# Unused_Modem_Pins.net
KiCad netlist of a schematic drawn in Altium Designer
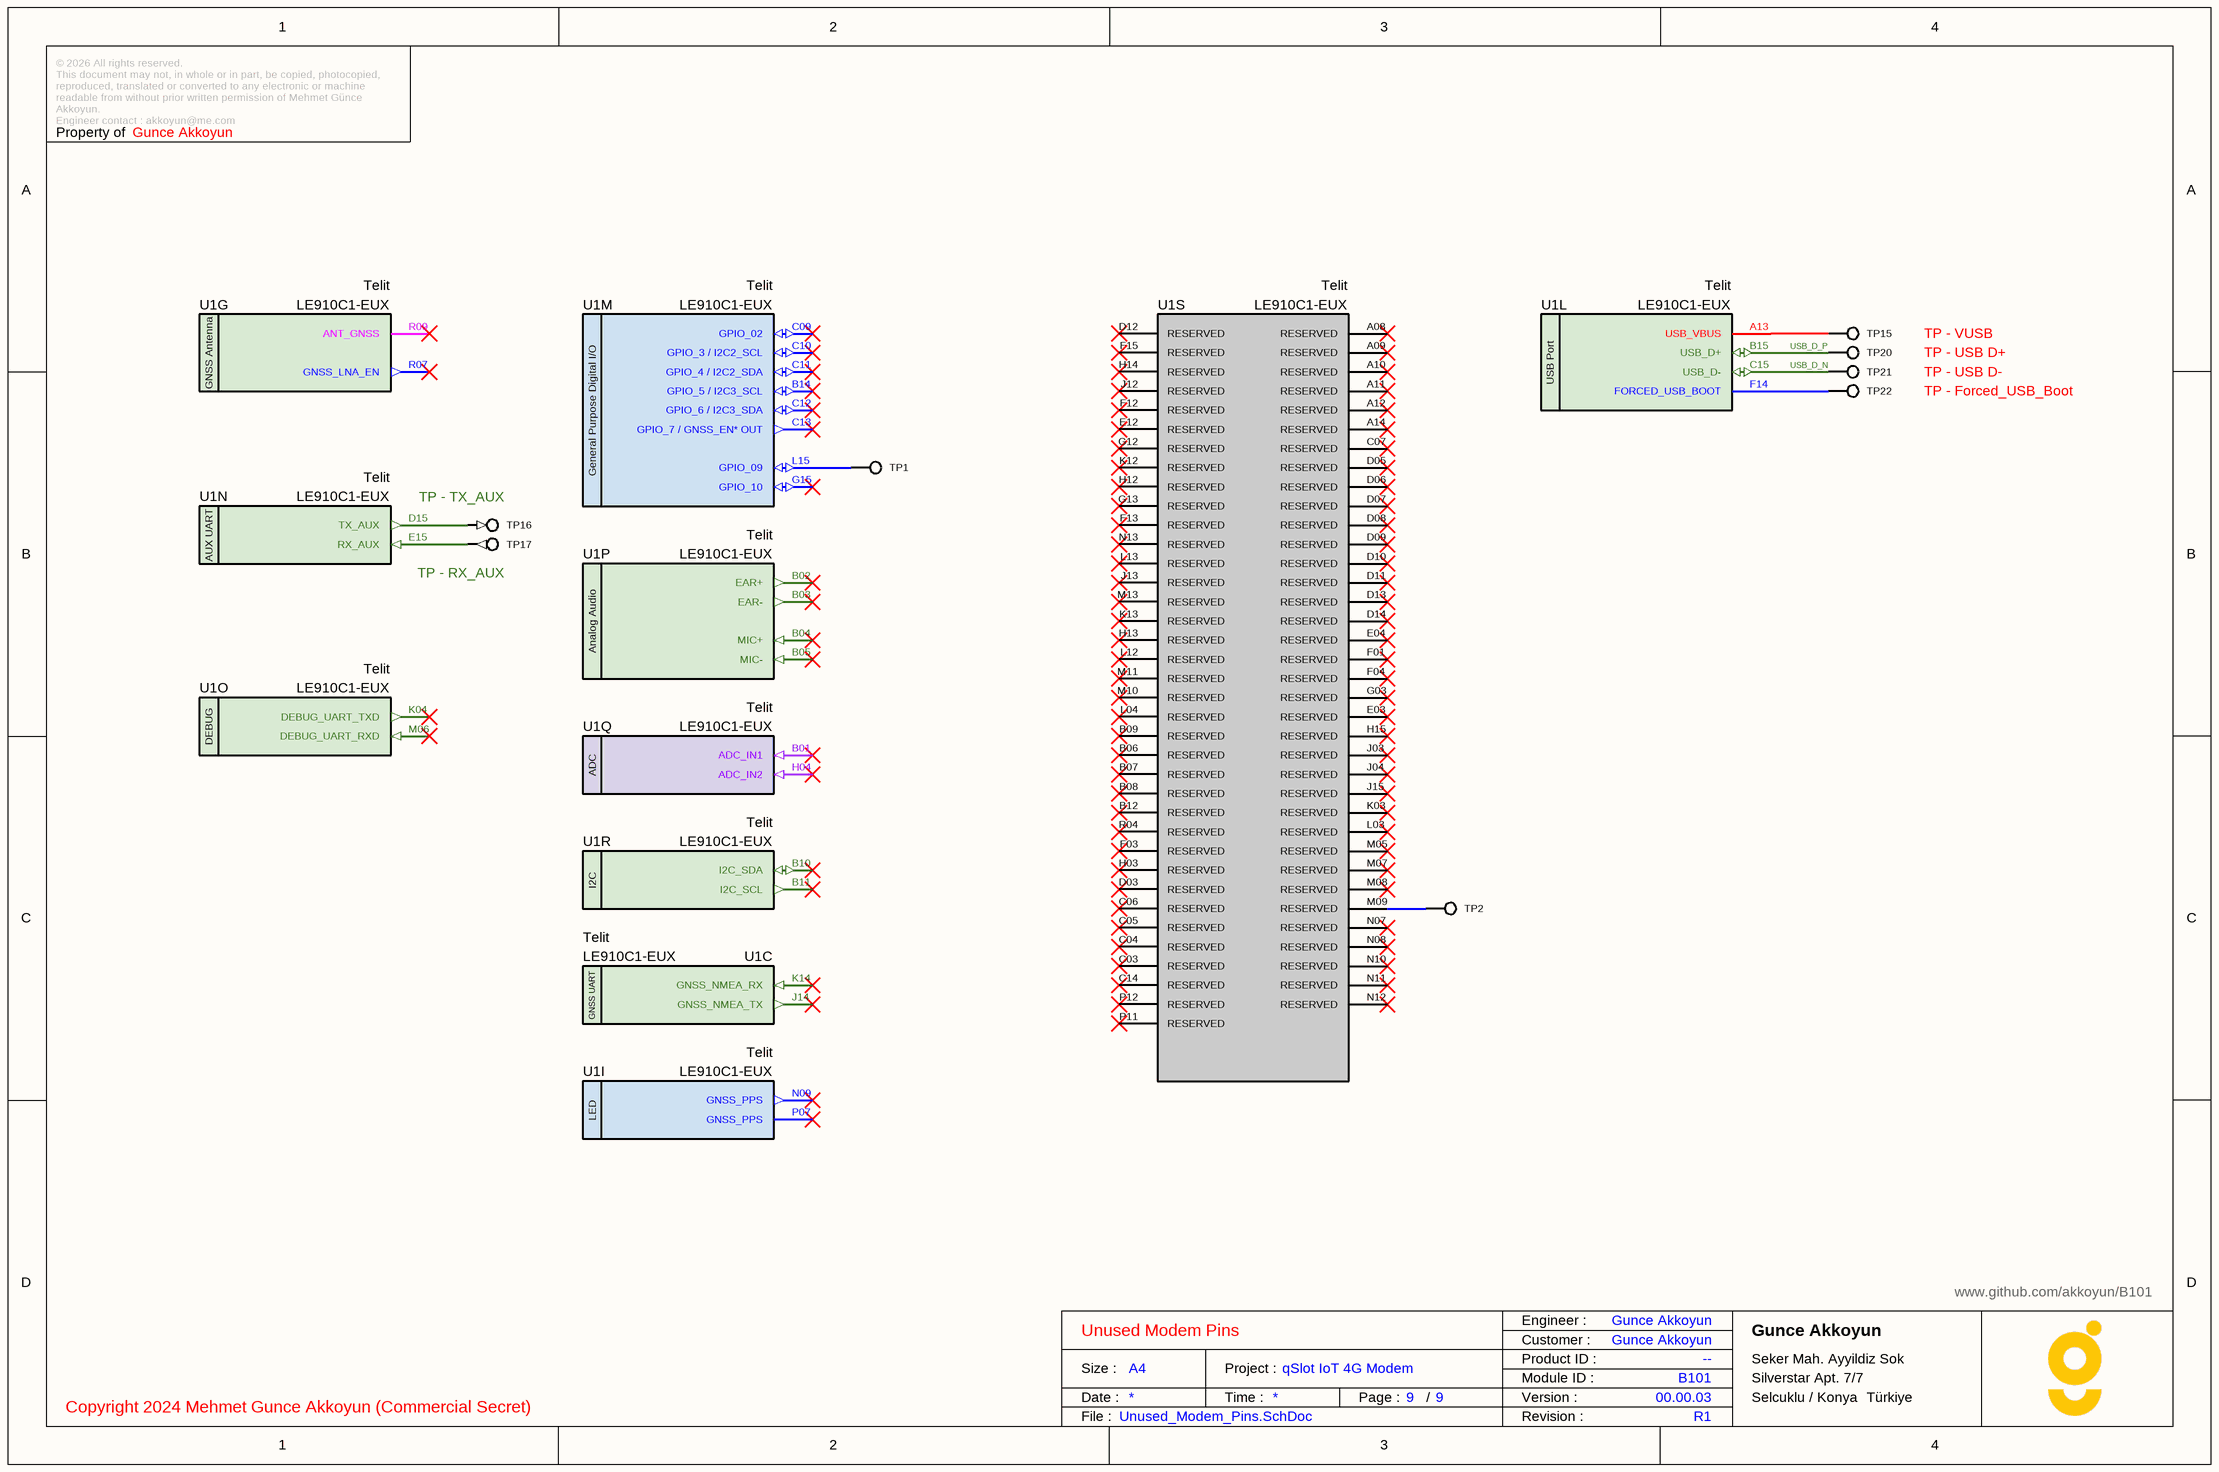
[diagram p0: Unused_Modem_Pins.SchDoc]

(export (version "E")
  (design (tool "Eeschema 10.0.6"))
  (components
    (comp (ref "TP1")
      (value "PCB - Test Point")
      (footprint "TP")
      (description "Test Point")
      (libsource (lib "Akkoyun") (part "PCB - Test Point"))
    )
    (comp (ref "TP2")
      (value "PCB - Test Point")
      (footprint "TP")
      (description "Test Point")
      (libsource (lib "Akkoyun") (part "PCB - Test Point"))
    )
    (comp (ref "TP15")
      (value "TP - VUSB")
      (footprint "TP")
      (description "Test Point")
      (libsource (lib "Akkoyun") (part "PCB - Test Point"))
    )
    (comp (ref "TP16")
      (value "TP - TX_AUX")
      (footprint "TP")
      (description "Test Point")
      (libsource (lib "Akkoyun") (part "PCB - Test Point"))
    )
    (comp (ref "TP17")
      (value "TP - RX_AUX")
      (footprint "TP")
      (description "Test Point")
      (libsource (lib "Akkoyun") (part "PCB - Test Point"))
    )
    (comp (ref "TP20")
      (value "TP - USB D+")
      (footprint "TP")
      (description "Test Point")
      (libsource (lib "Akkoyun") (part "PCB - Test Point"))
    )
    (comp (ref "TP21")
      (value "TP - USB D-")
      (footprint "TP")
      (description "Test Point")
      (libsource (lib "Akkoyun") (part "PCB - Test Point"))
    )
    (comp (ref "TP22")
      (value "TP - Forced_USB_Boot")
      (footprint "TP")
      (description "Test Point")
      (libsource (lib "Akkoyun") (part "PCB - Test Point"))
    )
    (comp (ref "U1")
      (value "LE910C1-EUX LTE GSM Module")
      (footprint "LE910 GSM Modem")
      (description "Telit LE910C1-EUX LTE/2G GSM Module")
      (fields
        (field (name "MANUFACTURER PART NUMBER") "LE910C1-EUX")
        (field (name "MANUFACTURER NAME") "Telit")
      )
      (libsource (lib "Akkoyun") (part "IC - LE910C1-EUX"))
    )
  )
  (nets
    (net (code "1") (name "/USB_D_N") (class "Default")
      (node (ref "TP21") (pin "1") (pinfunction "1_1") (pintype "output"))
      (node (ref "U1") (pin "C15") (pinfunction "USB_D-_C15") (pintype "bidirectional"))
    )
    (net (code "2") (name "/USB_D_P") (class "Default")
      (node (ref "TP20") (pin "1") (pinfunction "1_1") (pintype "output"))
      (node (ref "U1") (pin "B15") (pinfunction "USB_D+_B15") (pintype "bidirectional"))
    )
    (net (code "3") (name "Net-(TP2-Pad1)") (class "Default")
      (node (ref "TP2") (pin "1") (pinfunction "1_1") (pintype "output"))
      (node (ref "U1") (pin "M09") (pinfunction "RESERVED_M09") (pintype "passive"))
    )
    (net (code "4") (name "Net-(U1L-FORCED_USB_BOOT)") (class "Default")
      (node (ref "TP22") (pin "1") (pinfunction "1_1") (pintype "output"))
      (node (ref "U1") (pin "F14") (pinfunction "FORCED_USB_BOOT_F14") (pintype "passive"))
    )
    (net (code "5") (name "Net-(U1L-USB_VBUS)") (class "Default")
      (node (ref "TP15") (pin "1") (pinfunction "1_1") (pintype "output"))
      (node (ref "U1") (pin "A13") (pinfunction "USB_VBUS_A13") (pintype "power_in"))
    )
    (net (code "6") (name "Net-(U1M-GPIO_09)") (class "Default")
      (node (ref "TP1") (pin "1") (pinfunction "1_1") (pintype "output"))
      (node (ref "U1") (pin "L15") (pinfunction "GPIO_09_L15") (pintype "bidirectional"))
    )
    (net (code "7") (name "Net-(U1N-RX_AUX)") (class "Default")
      (node (ref "TP17") (pin "1") (pinfunction "1_1") (pintype "output"))
      (node (ref "U1") (pin "E15") (pinfunction "RX_AUX_E15") (pintype "input"))
    )
    (net (code "8") (name "Net-(U1N-TX_AUX)") (class "Default")
      (node (ref "TP16") (pin "1") (pinfunction "1_1") (pintype "output"))
      (node (ref "U1") (pin "D15") (pinfunction "TX_AUX_D15") (pintype "output"))
    )
    (net (code "9") (name "unconnected-(U1C-GNSS_NMEA_RX-PadK14)") (class "Default")
      (node (ref "U1") (pin "K14") (pinfunction "GNSS_NMEA_RX_K14") (pintype "input+no_connect"))
    )
    (net (code "10") (name "unconnected-(U1C-GNSS_NMEA_TX-PadJ14)") (class "Default")
      (node (ref "U1") (pin "J14") (pinfunction "GNSS_NMEA_TX_J14") (pintype "output+no_connect"))
    )
    (net (code "11") (name "unconnected-(U1G-ANT_GNSS-PadR09)") (class "Default")
      (node (ref "U1") (pin "R09") (pinfunction "ANT_GNSS_R09") (pintype "passive+no_connect"))
    )
    (net (code "12") (name "unconnected-(U1G-GNSS_LNA_EN-PadR07)") (class "Default")
      (node (ref "U1") (pin "R07") (pinfunction "GNSS_LNA_EN_R07") (pintype "output+no_connect"))
    )
    (net (code "13") (name "unconnected-(U1I-GNSS_PPS-PadN09)") (class "Default")
      (node (ref "U1") (pin "N09") (pinfunction "GNSS_PPS_N09") (pintype "output+no_connect"))
    )
    (net (code "14") (name "unconnected-(U1I-GNSS_PPS-PadP07)") (class "Default")
      (node (ref "U1") (pin "P07") (pinfunction "GNSS_PPS_P07") (pintype "passive+no_connect"))
    )
    (net (code "15") (name "unconnected-(U1M-GPIO_02-PadC09)") (class "Default")
      (node (ref "U1") (pin "C09") (pinfunction "GPIO_02_C09") (pintype "bidirectional+no_connect"))
    )
    (net (code "16") (name "unconnected-(U1M-GPIO_3_{slash}_I2C2_SCL-PadC10)") (class "Default")
      (node (ref "U1") (pin "C10") (pinfunction "GPIO_3_/_I2C2_SCL_C10") (pintype "bidirectional+no_connect"))
    )
    (net (code "17") (name "unconnected-(U1M-GPIO_4_{slash}_I2C2_SDA-PadC11)") (class "Default")
      (node (ref "U1") (pin "C11") (pinfunction "GPIO_4_/_I2C2_SDA_C11") (pintype "bidirectional+no_connect"))
    )
    (net (code "18") (name "unconnected-(U1M-GPIO_5_{slash}_I2C3_SCL-PadB14)") (class "Default")
      (node (ref "U1") (pin "B14") (pinfunction "GPIO_5_/_I2C3_SCL_B14") (pintype "bidirectional+no_connect"))
    )
    (net (code "19") (name "unconnected-(U1M-GPIO_6_{slash}_I2C3_SDA-PadC12)") (class "Default")
      (node (ref "U1") (pin "C12") (pinfunction "GPIO_6_/_I2C3_SDA_C12") (pintype "bidirectional+no_connect"))
    )
    (net (code "20") (name "unconnected-(U1M-GPIO_7_{slash}_GNSS_EN*_OUT-PadC13)") (class "Default")
      (node (ref "U1") (pin "C13") (pinfunction "GPIO_7_/_GNSS_EN*_OUT_C13") (pintype "output+no_connect"))
    )
    (net (code "21") (name "unconnected-(U1M-GPIO_10-PadG15)") (class "Default")
      (node (ref "U1") (pin "G15") (pinfunction "GPIO_10_G15") (pintype "bidirectional+no_connect"))
    )
    (net (code "22") (name "unconnected-(U1O-DEBUG_UART_RXD-PadM06)") (class "Default")
      (node (ref "U1") (pin "M06") (pinfunction "DEBUG_UART_RXD_M06") (pintype "input+no_connect"))
    )
    (net (code "23") (name "unconnected-(U1O-DEBUG_UART_TXD-PadK04)") (class "Default")
      (node (ref "U1") (pin "K04") (pinfunction "DEBUG_UART_TXD_K04") (pintype "output+no_connect"))
    )
    (net (code "24") (name "unconnected-(U1P-EAR+-PadB02)") (class "Default")
      (node (ref "U1") (pin "B02") (pinfunction "EAR+_B02") (pintype "output+no_connect"))
    )
    (net (code "25") (name "unconnected-(U1P-EAR--PadB03)") (class "Default")
      (node (ref "U1") (pin "B03") (pinfunction "EAR-_B03") (pintype "output+no_connect"))
    )
    (net (code "26") (name "unconnected-(U1P-MIC+-PadB04)") (class "Default")
      (node (ref "U1") (pin "B04") (pinfunction "MIC+_B04") (pintype "input+no_connect"))
    )
    (net (code "27") (name "unconnected-(U1P-MIC--PadB05)") (class "Default")
      (node (ref "U1") (pin "B05") (pinfunction "MIC-_B05") (pintype "input+no_connect"))
    )
    (net (code "28") (name "unconnected-(U1Q-ADC_IN1-PadB01)") (class "Default")
      (node (ref "U1") (pin "B01") (pinfunction "ADC_IN1_B01") (pintype "input+no_connect"))
    )
    (net (code "29") (name "unconnected-(U1Q-ADC_IN2-PadH04)") (class "Default")
      (node (ref "U1") (pin "H04") (pinfunction "ADC_IN2_H04") (pintype "input+no_connect"))
    )
    (net (code "30") (name "unconnected-(U1R-I2C_SCL-PadB11)") (class "Default")
      (node (ref "U1") (pin "B11") (pinfunction "I2C_SCL_B11") (pintype "output+no_connect"))
    )
    (net (code "31") (name "unconnected-(U1R-I2C_SDA-PadB10)") (class "Default")
      (node (ref "U1") (pin "B10") (pinfunction "I2C_SDA_B10") (pintype "bidirectional+no_connect"))
    )
    (net (code "32") (name "unconnected-(U1S-RESERVED-PadA08)") (class "Default")
      (node (ref "U1") (pin "A08") (pinfunction "RESERVED_A08") (pintype "passive+no_connect"))
    )
    (net (code "33") (name "unconnected-(U1S-RESERVED-PadA09)") (class "Default")
      (node (ref "U1") (pin "A09") (pinfunction "RESERVED_A09") (pintype "passive+no_connect"))
    )
    (net (code "34") (name "unconnected-(U1S-RESERVED-PadA10)") (class "Default")
      (node (ref "U1") (pin "A10") (pinfunction "RESERVED_A10") (pintype "passive+no_connect"))
    )
    (net (code "35") (name "unconnected-(U1S-RESERVED-PadA11)") (class "Default")
      (node (ref "U1") (pin "A11") (pinfunction "RESERVED_A11") (pintype "passive+no_connect"))
    )
    (net (code "36") (name "unconnected-(U1S-RESERVED-PadA12)") (class "Default")
      (node (ref "U1") (pin "A12") (pinfunction "RESERVED_A12") (pintype "passive+no_connect"))
    )
    (net (code "37") (name "unconnected-(U1S-RESERVED-PadA14)") (class "Default")
      (node (ref "U1") (pin "A14") (pinfunction "RESERVED_A14") (pintype "passive+no_connect"))
    )
    (net (code "38") (name "unconnected-(U1S-RESERVED-PadB06)") (class "Default")
      (node (ref "U1") (pin "B06") (pinfunction "RESERVED_B06") (pintype "passive+no_connect"))
    )
    (net (code "39") (name "unconnected-(U1S-RESERVED-PadB07)") (class "Default")
      (node (ref "U1") (pin "B07") (pinfunction "RESERVED_B07") (pintype "passive+no_connect"))
    )
    (net (code "40") (name "unconnected-(U1S-RESERVED-PadB08)") (class "Default")
      (node (ref "U1") (pin "B08") (pinfunction "RESERVED_B08") (pintype "passive+no_connect"))
    )
    (net (code "41") (name "unconnected-(U1S-RESERVED-PadB09)") (class "Default")
      (node (ref "U1") (pin "B09") (pinfunction "RESERVED_B09") (pintype "passive+no_connect"))
    )
    (net (code "42") (name "unconnected-(U1S-RESERVED-PadB12)") (class "Default")
      (node (ref "U1") (pin "B12") (pinfunction "RESERVED_B12") (pintype "passive+no_connect"))
    )
    (net (code "43") (name "unconnected-(U1S-RESERVED-PadC03)") (class "Default")
      (node (ref "U1") (pin "C03") (pinfunction "RESERVED_C03") (pintype "passive+no_connect"))
    )
    (net (code "44") (name "unconnected-(U1S-RESERVED-PadC04)") (class "Default")
      (node (ref "U1") (pin "C04") (pinfunction "RESERVED_C04") (pintype "passive+no_connect"))
    )
    (net (code "45") (name "unconnected-(U1S-RESERVED-PadC05)") (class "Default")
      (node (ref "U1") (pin "C05") (pinfunction "RESERVED_C05") (pintype "passive+no_connect"))
    )
    (net (code "46") (name "unconnected-(U1S-RESERVED-PadC06)") (class "Default")
      (node (ref "U1") (pin "C06") (pinfunction "RESERVED_C06") (pintype "passive+no_connect"))
    )
    (net (code "47") (name "unconnected-(U1S-RESERVED-PadC07)") (class "Default")
      (node (ref "U1") (pin "C07") (pinfunction "RESERVED_C07") (pintype "passive+no_connect"))
    )
    (net (code "48") (name "unconnected-(U1S-RESERVED-PadC14)") (class "Default")
      (node (ref "U1") (pin "C14") (pinfunction "RESERVED_C14") (pintype "passive+no_connect"))
    )
    (net (code "49") (name "unconnected-(U1S-RESERVED-PadD03)") (class "Default")
      (node (ref "U1") (pin "D03") (pinfunction "RESERVED_D03") (pintype "passive+no_connect"))
    )
    (net (code "50") (name "unconnected-(U1S-RESERVED-PadD05)") (class "Default")
      (node (ref "U1") (pin "D05") (pinfunction "RESERVED_D05") (pintype "passive+no_connect"))
    )
    (net (code "51") (name "unconnected-(U1S-RESERVED-PadD06)") (class "Default")
      (node (ref "U1") (pin "D06") (pinfunction "RESERVED_D06") (pintype "passive+no_connect"))
    )
    (net (code "52") (name "unconnected-(U1S-RESERVED-PadD07)") (class "Default")
      (node (ref "U1") (pin "D07") (pinfunction "RESERVED_D07") (pintype "passive+no_connect"))
    )
    (net (code "53") (name "unconnected-(U1S-RESERVED-PadD08)") (class "Default")
      (node (ref "U1") (pin "D08") (pinfunction "RESERVED_D08") (pintype "passive+no_connect"))
    )
    (net (code "54") (name "unconnected-(U1S-RESERVED-PadD09)") (class "Default")
      (node (ref "U1") (pin "D09") (pinfunction "RESERVED_D09") (pintype "passive+no_connect"))
    )
    (net (code "55") (name "unconnected-(U1S-RESERVED-PadD10)") (class "Default")
      (node (ref "U1") (pin "D10") (pinfunction "RESERVED_D10") (pintype "passive+no_connect"))
    )
    (net (code "56") (name "unconnected-(U1S-RESERVED-PadD11)") (class "Default")
      (node (ref "U1") (pin "D11") (pinfunction "RESERVED_D11") (pintype "passive+no_connect"))
    )
    (net (code "57") (name "unconnected-(U1S-RESERVED-PadD12)") (class "Default")
      (node (ref "U1") (pin "D12") (pinfunction "RESERVED_D12") (pintype "passive+no_connect"))
    )
    (net (code "58") (name "unconnected-(U1S-RESERVED-PadD13)") (class "Default")
      (node (ref "U1") (pin "D13") (pinfunction "RESERVED_D13") (pintype "passive+no_connect"))
    )
    (net (code "59") (name "unconnected-(U1S-RESERVED-PadD14)") (class "Default")
      (node (ref "U1") (pin "D14") (pinfunction "RESERVED_D14") (pintype "passive+no_connect"))
    )
    (net (code "60") (name "unconnected-(U1S-RESERVED-PadE03)") (class "Default")
      (node (ref "U1") (pin "E03") (pinfunction "RESERVED_E03") (pintype "passive+no_connect"))
    )
    (net (code "61") (name "unconnected-(U1S-RESERVED-PadE04)") (class "Default")
      (node (ref "U1") (pin "E04") (pinfunction "RESERVED_E04") (pintype "passive+no_connect"))
    )
    (net (code "62") (name "unconnected-(U1S-RESERVED-PadE12)") (class "Default")
      (node (ref "U1") (pin "E12") (pinfunction "RESERVED_E12") (pintype "passive+no_connect"))
    )
    (net (code "63") (name "unconnected-(U1S-RESERVED-PadF01)") (class "Default")
      (node (ref "U1") (pin "F01") (pinfunction "RESERVED_F01") (pintype "passive+no_connect"))
    )
    (net (code "64") (name "unconnected-(U1S-RESERVED-PadF03)") (class "Default")
      (node (ref "U1") (pin "F03") (pinfunction "RESERVED_F03") (pintype "passive+no_connect"))
    )
    (net (code "65") (name "unconnected-(U1S-RESERVED-PadF04)") (class "Default")
      (node (ref "U1") (pin "F04") (pinfunction "RESERVED_F04") (pintype "passive+no_connect"))
    )
    (net (code "66") (name "unconnected-(U1S-RESERVED-PadF12)") (class "Default")
      (node (ref "U1") (pin "F12") (pinfunction "RESERVED_F12") (pintype "passive+no_connect"))
    )
    (net (code "67") (name "unconnected-(U1S-RESERVED-PadF13)") (class "Default")
      (node (ref "U1") (pin "F13") (pinfunction "RESERVED_F13") (pintype "passive+no_connect"))
    )
    (net (code "68") (name "unconnected-(U1S-RESERVED-PadF15)") (class "Default")
      (node (ref "U1") (pin "F15") (pinfunction "RESERVED_F15") (pintype "passive+no_connect"))
    )
    (net (code "69") (name "unconnected-(U1S-RESERVED-PadG03)") (class "Default")
      (node (ref "U1") (pin "G03") (pinfunction "RESERVED_G03") (pintype "passive+no_connect"))
    )
    (net (code "70") (name "unconnected-(U1S-RESERVED-PadG12)") (class "Default")
      (node (ref "U1") (pin "G12") (pinfunction "RESERVED_G12") (pintype "passive+no_connect"))
    )
    (net (code "71") (name "unconnected-(U1S-RESERVED-PadG13)") (class "Default")
      (node (ref "U1") (pin "G13") (pinfunction "RESERVED_G13") (pintype "passive+no_connect"))
    )
    (net (code "72") (name "unconnected-(U1S-RESERVED-PadH03)") (class "Default")
      (node (ref "U1") (pin "H03") (pinfunction "RESERVED_H03") (pintype "passive+no_connect"))
    )
    (net (code "73") (name "unconnected-(U1S-RESERVED-PadH12)") (class "Default")
      (node (ref "U1") (pin "H12") (pinfunction "RESERVED_H12") (pintype "passive+no_connect"))
    )
    (net (code "74") (name "unconnected-(U1S-RESERVED-PadH13)") (class "Default")
      (node (ref "U1") (pin "H13") (pinfunction "RESERVED_H13") (pintype "passive+no_connect"))
    )
    (net (code "75") (name "unconnected-(U1S-RESERVED-PadH14)") (class "Default")
      (node (ref "U1") (pin "H14") (pinfunction "RESERVED_H14") (pintype "passive+no_connect"))
    )
    (net (code "76") (name "unconnected-(U1S-RESERVED-PadH15)") (class "Default")
      (node (ref "U1") (pin "H15") (pinfunction "RESERVED_H15") (pintype "passive+no_connect"))
    )
    (net (code "77") (name "unconnected-(U1S-RESERVED-PadJ03)") (class "Default")
      (node (ref "U1") (pin "J03") (pinfunction "RESERVED_J03") (pintype "passive+no_connect"))
    )
    (net (code "78") (name "unconnected-(U1S-RESERVED-PadJ04)") (class "Default")
      (node (ref "U1") (pin "J04") (pinfunction "RESERVED_J04") (pintype "passive+no_connect"))
    )
    (net (code "79") (name "unconnected-(U1S-RESERVED-PadJ12)") (class "Default")
      (node (ref "U1") (pin "J12") (pinfunction "RESERVED_J12") (pintype "passive+no_connect"))
    )
    (net (code "80") (name "unconnected-(U1S-RESERVED-PadJ13)") (class "Default")
      (node (ref "U1") (pin "J13") (pinfunction "RESERVED_J13") (pintype "passive+no_connect"))
    )
    (net (code "81") (name "unconnected-(U1S-RESERVED-PadJ15)") (class "Default")
      (node (ref "U1") (pin "J15") (pinfunction "RESERVED_J15") (pintype "passive+no_connect"))
    )
    (net (code "82") (name "unconnected-(U1S-RESERVED-PadK03)") (class "Default")
      (node (ref "U1") (pin "K03") (pinfunction "RESERVED_K03") (pintype "passive+no_connect"))
    )
    (net (code "83") (name "unconnected-(U1S-RESERVED-PadK12)") (class "Default")
      (node (ref "U1") (pin "K12") (pinfunction "RESERVED_K12") (pintype "passive+no_connect"))
    )
    (net (code "84") (name "unconnected-(U1S-RESERVED-PadK13)") (class "Default")
      (node (ref "U1") (pin "K13") (pinfunction "RESERVED_K13") (pintype "passive+no_connect"))
    )
    (net (code "85") (name "unconnected-(U1S-RESERVED-PadL03)") (class "Default")
      (node (ref "U1") (pin "L03") (pinfunction "RESERVED_L03") (pintype "passive+no_connect"))
    )
    (net (code "86") (name "unconnected-(U1S-RESERVED-PadL04)") (class "Default")
      (node (ref "U1") (pin "L04") (pinfunction "RESERVED_L04") (pintype "passive+no_connect"))
    )
    (net (code "87") (name "unconnected-(U1S-RESERVED-PadL12)") (class "Default")
      (node (ref "U1") (pin "L12") (pinfunction "RESERVED_L12") (pintype "passive+no_connect"))
    )
    (net (code "88") (name "unconnected-(U1S-RESERVED-PadL13)") (class "Default")
      (node (ref "U1") (pin "L13") (pinfunction "RESERVED_L13") (pintype "passive+no_connect"))
    )
    (net (code "89") (name "unconnected-(U1S-RESERVED-PadM05)") (class "Default")
      (node (ref "U1") (pin "M05") (pinfunction "RESERVED_M05") (pintype "passive+no_connect"))
    )
    (net (code "90") (name "unconnected-(U1S-RESERVED-PadM07)") (class "Default")
      (node (ref "U1") (pin "M07") (pinfunction "RESERVED_M07") (pintype "passive+no_connect"))
    )
    (net (code "91") (name "unconnected-(U1S-RESERVED-PadM08)") (class "Default")
      (node (ref "U1") (pin "M08") (pinfunction "RESERVED_M08") (pintype "passive+no_connect"))
    )
    (net (code "92") (name "unconnected-(U1S-RESERVED-PadM10)") (class "Default")
      (node (ref "U1") (pin "M10") (pinfunction "RESERVED_M10") (pintype "passive+no_connect"))
    )
    (net (code "93") (name "unconnected-(U1S-RESERVED-PadM11)") (class "Default")
      (node (ref "U1") (pin "M11") (pinfunction "RESERVED_M11") (pintype "passive+no_connect"))
    )
    (net (code "94") (name "unconnected-(U1S-RESERVED-PadM13)") (class "Default")
      (node (ref "U1") (pin "M13") (pinfunction "RESERVED_M13") (pintype "passive+no_connect"))
    )
    (net (code "95") (name "unconnected-(U1S-RESERVED-PadN07)") (class "Default")
      (node (ref "U1") (pin "N07") (pinfunction "RESERVED_N07") (pintype "passive+no_connect"))
    )
    (net (code "96") (name "unconnected-(U1S-RESERVED-PadN08)") (class "Default")
      (node (ref "U1") (pin "N08") (pinfunction "RESERVED_N08") (pintype "passive+no_connect"))
    )
    (net (code "97") (name "unconnected-(U1S-RESERVED-PadN10)") (class "Default")
      (node (ref "U1") (pin "N10") (pinfunction "RESERVED_N10") (pintype "passive+no_connect"))
    )
    (net (code "98") (name "unconnected-(U1S-RESERVED-PadN11)") (class "Default")
      (node (ref "U1") (pin "N11") (pinfunction "RESERVED_N11") (pintype "passive+no_connect"))
    )
    (net (code "99") (name "unconnected-(U1S-RESERVED-PadN12)") (class "Default")
      (node (ref "U1") (pin "N12") (pinfunction "RESERVED_N12") (pintype "passive+no_connect"))
    )
    (net (code "100") (name "unconnected-(U1S-RESERVED-PadN13)") (class "Default")
      (node (ref "U1") (pin "N13") (pinfunction "RESERVED_N13") (pintype "passive+no_connect"))
    )
    (net (code "101") (name "unconnected-(U1S-RESERVED-PadP11)") (class "Default")
      (node (ref "U1") (pin "P11") (pinfunction "RESERVED_P11") (pintype "passive+no_connect"))
    )
    (net (code "102") (name "unconnected-(U1S-RESERVED-PadP12)") (class "Default")
      (node (ref "U1") (pin "P12") (pinfunction "RESERVED_P12") (pintype "passive+no_connect"))
    )
    (net (code "103") (name "unconnected-(U1S-RESERVED-PadR04)") (class "Default")
      (node (ref "U1") (pin "R04") (pinfunction "RESERVED_R04") (pintype "power_in+no_connect"))
    )
  )
)
